# EEM_Connectors.net
KiCad netlist of a schematic drawn in Altium Designer
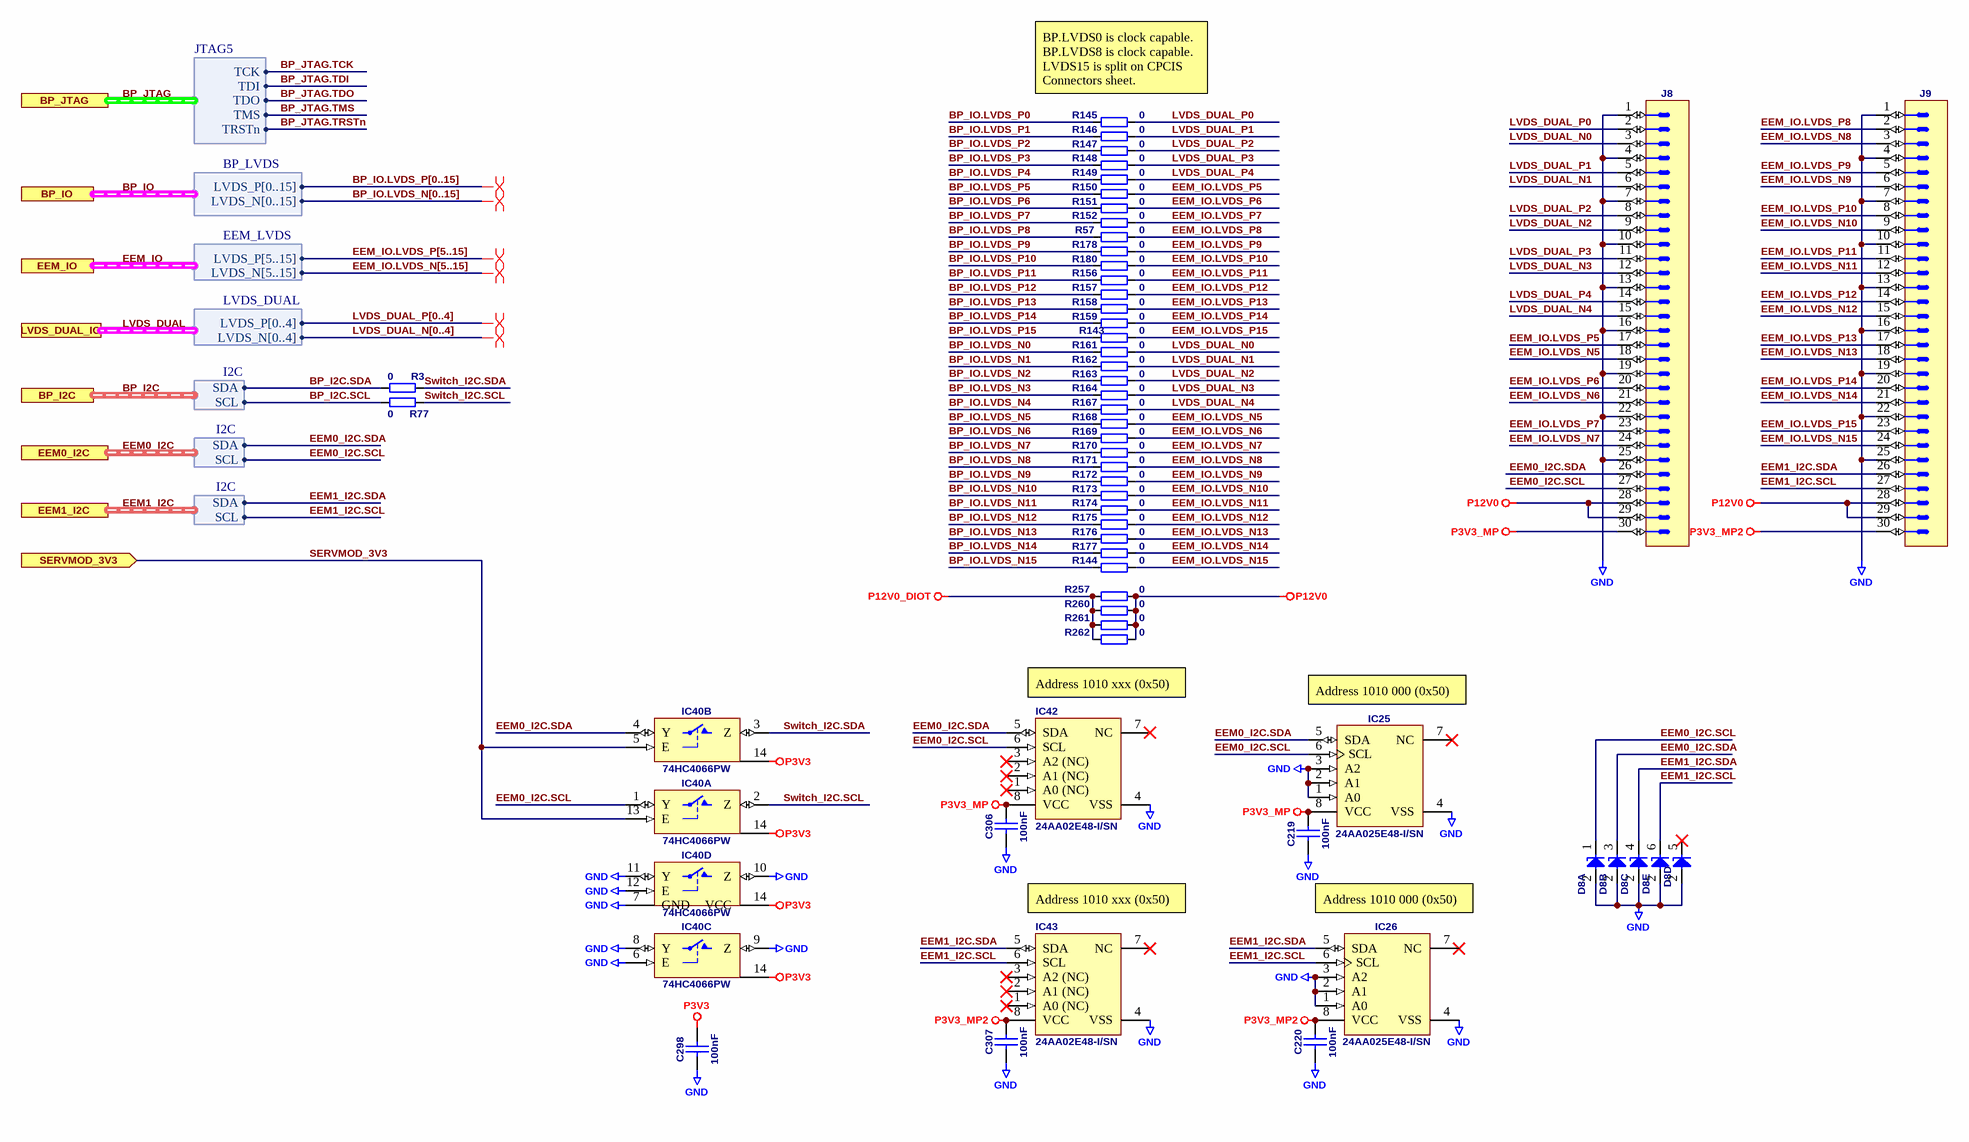
[diagram p0: EEM_Connectors.SchDoc]

(export (version "E")
  (design (tool "Eeschema 10.0.6"))
  (components
    (comp (ref "C219")
      (value "100nF")
      (footprint "CAPC1005X55N")
      (description "Non-polarised capacitor")
      (fields
        (field (name "PART NUMBER") "CC0402_100NF_25V_10%_X7R_YUDEN_TMK105B7104KVHF")
        (field (name "VOLTAGE") "25V")
        (field (name "AUTHOR") "CERN DEM JLC")
      )
      (libsource (lib "Capacitors") (part "Capacitor - non polarized"))
    )
    (comp (ref "C220")
      (value "100nF")
      (footprint "CAPC1005X55N")
      (description "Non-polarised capacitor")
      (fields
        (field (name "PART NUMBER") "CC0402_100NF_16V_10%_X5R")
        (field (name "VOLTAGE") "16V")
        (field (name "AUTHOR") "CERN DEM JLC")
      )
      (libsource (lib "Capacitors") (part "Capacitor - non polarized"))
    )
    (comp (ref "C298")
      (value "100nF")
      (footprint "CAPC1005X55N")
      (description "Non-polarised capacitor")
      (fields
        (field (name "PART NUMBER") "CC0402_100NF_16V_10%_X5R")
        (field (name "VOLTAGE") "16V")
        (field (name "AUTHOR") "CERN DEM JLC")
      )
      (libsource (lib "Capacitors") (part "Capacitor - non polarized"))
    )
    (comp (ref "C306")
      (value "100nF")
      (footprint "CAPC1005X55N")
      (description "Non-polarised capacitor")
      (fields
        (field (name "PART NUMBER") "CC0402_100NF_25V_10%_X7R_YUDEN_TMK105B7104KVHF")
        (field (name "VOLTAGE") "25V")
        (field (name "AUTHOR") "CERN DEM JLC")
      )
      (libsource (lib "Capacitors") (part "Capacitor - non polarized"))
    )
    (comp (ref "C307")
      (value "100nF")
      (footprint "CAPC1005X55N")
      (description "Non-polarised capacitor")
      (fields
        (field (name "PART NUMBER") "CC0402_100NF_25V_10%_X7R_YUDEN_TMK105B7104KVHF")
        (field (name "VOLTAGE") "25V")
        (field (name "AUTHOR") "CERN DEM JLC")
      )
      (libsource (lib "Capacitors") (part "Capacitor - non polarized"))
    )
    (comp (ref "D8")
      (value "PESD3V3L5UY")
      (footprint "SOT65P210X110-6N")
      (description "Fivefold ESD Protection Diode Arrays")
      (fields
        (field (name "VOLTAGE") "3.3V")
        (field (name "POWER") "200W")
        (field (name "AUTHOR") "CERN DEM WB")
      )
      (libsource (lib "ICs And Semiconductors") (part "PESD Array 5diodes 6pins Common anode2"))
    )
    (comp (ref "IC25")
      (value "24AA025E48-I/SN")
      (footprint "SOIC127P600X175-8N")
      (description "1.7V-5.5V, 2K I2C™ Serial EEPROMs with EUI-48™ Node Identity")
      (fields (field (name "MANUFACTURER") "MICROCHIP TECHNOLOGY") (field (name "AUTHOR") "CERN DEM MR"))
      (libsource (lib "ICs And Semiconductors") (part "24AA025E48-I/SN"))
    )
    (comp (ref "IC26")
      (value "24AA025E48-I/SN")
      (footprint "SOIC127P600X175-8N")
      (description "1.7V-5.5V, 2K I2C™ Serial EEPROMs with EUI-48™ Node Identity")
      (fields (field (name "MANUFACTURER") "MICROCHIP TECHNOLOGY") (field (name "AUTHOR") "CERN DEM MR"))
      (libsource (lib "ICs And Semiconductors") (part "24AA025E48-I/SN"))
    )
    (comp (ref "IC40")
      (value "74HC4066PW")
      (footprint "SOP65P640X110-14N")
      (fields (field (name "MANUFACTURER") "NXP SEMICONDUCTORS") (field (name "AUTHOR") "CERN DEM JLC"))
      (libsource (lib "ICs And Semiconductors") (part "4066"))
    )
    (comp (ref "IC42")
      (value "24AA02E48-I/SN")
      (footprint "SOIC127P600X175-8N")
      (description "1.7V-5.5V, 2K I2C™ Serial EEPROMs with EUI-48™ Node Identity")
      (libsource (lib "Integrated_Library_MP") (part "24AA02E48-I/SN"))
    )
    (comp (ref "IC43")
      (value "24AA02E48-I/SN")
      (footprint "SOIC127P600X175-8N")
      (description "1.7V-5.5V, 2K I2C™ Serial EEPROMs with EUI-48™ Node Identity")
      (libsource (lib "Integrated_Library_MP") (part "24AA02E48-I/SN"))
    )
    (comp (ref "J8")
      (value "~")
      (footprint "3M_N2530-6002RB")
      (description "Connector 30 Male")
      (fields
        (field (name "PART NUMBER") "3M_N2530-6002RB")
        (field (name "MANUFACTURER") "3M")
        (field (name "AUTHOR") "CERN DEM JLC")
      )
      (libsource (lib "Connectors") (part "Connector 30 Male"))
    )
    (comp (ref "J9")
      (value "~")
      (footprint "3M_N2530-6002RB")
      (description "Connector 30 Male")
      (fields
        (field (name "PART NUMBER") "3M_N2530-6002RB")
        (field (name "MANUFACTURER") "3M")
        (field (name "AUTHOR") "CERN DEM JLC")
      )
      (libsource (lib "Connectors") (part "Connector 30 Male"))
    )
    (comp (ref "R3")
      (value "0")
      (footprint "RESC1005X40N")
      (description "Resistor")
      (fields
        (field (name "PART NUMBER") "R0402_0R_JUMPER")
        (field (name "MANUFACTURER") "GENERIC")
        (field (name "AUTHOR") "CERN DEM JLC")
      )
      (libsource (lib "Resistors") (part "Resistor"))
    )
    (comp (ref "R57")
      (value "0")
      (footprint "RESC1005X40N")
      (description "Resistor")
      (fields
        (field (name "PART NUMBER") "R0402_0R_JUMPER")
        (field (name "MANUFACTURER") "GENERIC")
        (field (name "AUTHOR") "CERN DEM JLC")
      )
      (libsource (lib "Resistors") (part "Resistor"))
    )
    (comp (ref "R77")
      (value "0")
      (footprint "RESC1005X40N")
      (description "Resistor")
      (fields
        (field (name "PART NUMBER") "R0402_0R_JUMPER")
        (field (name "MANUFACTURER") "GENERIC")
        (field (name "AUTHOR") "CERN DEM JLC")
      )
      (libsource (lib "Resistors") (part "Resistor"))
    )
    (comp (ref "R143")
      (value "0")
      (footprint "RESC1005X40N")
      (description "Resistor")
      (fields
        (field (name "PART NUMBER") "R0402_0R_JUMPER")
        (field (name "MANUFACTURER") "GENERIC")
        (field (name "AUTHOR") "CERN DEM JLC")
      )
      (libsource (lib "Resistors") (part "Resistor"))
    )
    (comp (ref "R144")
      (value "0")
      (footprint "RESC1005X40N")
      (description "Resistor")
      (fields
        (field (name "PART NUMBER") "R0402_0R_JUMPER")
        (field (name "MANUFACTURER") "GENERIC")
        (field (name "AUTHOR") "CERN DEM JLC")
      )
      (libsource (lib "Resistors") (part "Resistor"))
    )
    (comp (ref "R145")
      (value "0")
      (footprint "RESC1005X40N")
      (description "Resistor")
      (fields
        (field (name "PART NUMBER") "R0402_0R_JUMPER")
        (field (name "MANUFACTURER") "GENERIC")
        (field (name "AUTHOR") "CERN DEM JLC")
      )
      (libsource (lib "Resistors") (part "Resistor"))
    )
    (comp (ref "R146")
      (value "0")
      (footprint "RESC1005X40N")
      (description "Resistor")
      (fields
        (field (name "PART NUMBER") "R0402_0R_JUMPER")
        (field (name "MANUFACTURER") "GENERIC")
        (field (name "AUTHOR") "CERN DEM JLC")
      )
      (libsource (lib "Resistors") (part "Resistor"))
    )
    (comp (ref "R147")
      (value "0")
      (footprint "RESC1005X40N")
      (description "Resistor")
      (fields
        (field (name "PART NUMBER") "R0402_0R_JUMPER")
        (field (name "MANUFACTURER") "GENERIC")
        (field (name "AUTHOR") "CERN DEM JLC")
      )
      (libsource (lib "Resistors") (part "Resistor"))
    )
    (comp (ref "R148")
      (value "0")
      (footprint "RESC1005X40N")
      (description "Resistor")
      (fields
        (field (name "PART NUMBER") "R0402_0R_JUMPER")
        (field (name "MANUFACTURER") "GENERIC")
        (field (name "AUTHOR") "CERN DEM JLC")
      )
      (libsource (lib "Resistors") (part "Resistor"))
    )
    (comp (ref "R149")
      (value "0")
      (footprint "RESC1005X40N")
      (description "Resistor")
      (fields
        (field (name "PART NUMBER") "R0402_0R_JUMPER")
        (field (name "MANUFACTURER") "GENERIC")
        (field (name "AUTHOR") "CERN DEM JLC")
      )
      (libsource (lib "Resistors") (part "Resistor"))
    )
    (comp (ref "R150")
      (value "0")
      (footprint "RESC1005X40N")
      (description "Resistor")
      (fields
        (field (name "PART NUMBER") "R0402_0R_JUMPER")
        (field (name "MANUFACTURER") "GENERIC")
        (field (name "AUTHOR") "CERN DEM JLC")
      )
      (libsource (lib "Resistors") (part "Resistor"))
    )
    (comp (ref "R151")
      (value "0")
      (footprint "RESC1005X40N")
      (description "Resistor")
      (fields
        (field (name "PART NUMBER") "R0402_0R_JUMPER")
        (field (name "MANUFACTURER") "GENERIC")
        (field (name "AUTHOR") "CERN DEM JLC")
      )
      (libsource (lib "Resistors") (part "Resistor"))
    )
    (comp (ref "R152")
      (value "0")
      (footprint "RESC1005X40N")
      (description "Resistor")
      (fields
        (field (name "PART NUMBER") "R0402_0R_JUMPER")
        (field (name "MANUFACTURER") "GENERIC")
        (field (name "AUTHOR") "CERN DEM JLC")
      )
      (libsource (lib "Resistors") (part "Resistor"))
    )
    (comp (ref "R156")
      (value "0")
      (footprint "RESC1005X40N")
      (description "Resistor")
      (fields
        (field (name "PART NUMBER") "R0402_0R_JUMPER")
        (field (name "MANUFACTURER") "GENERIC")
        (field (name "AUTHOR") "CERN DEM JLC")
      )
      (libsource (lib "Resistors") (part "Resistor"))
    )
    (comp (ref "R157")
      (value "0")
      (footprint "RESC1005X40N")
      (description "Resistor")
      (fields
        (field (name "PART NUMBER") "R0402_0R_JUMPER")
        (field (name "MANUFACTURER") "GENERIC")
        (field (name "AUTHOR") "CERN DEM JLC")
      )
      (libsource (lib "Resistors") (part "Resistor"))
    )
    (comp (ref "R158")
      (value "0")
      (footprint "RESC1005X40N")
      (description "Resistor")
      (fields
        (field (name "PART NUMBER") "R0402_0R_JUMPER")
        (field (name "MANUFACTURER") "GENERIC")
        (field (name "AUTHOR") "CERN DEM JLC")
      )
      (libsource (lib "Resistors") (part "Resistor"))
    )
    (comp (ref "R159")
      (value "0")
      (footprint "RESC1005X40N")
      (description "Resistor")
      (fields
        (field (name "PART NUMBER") "R0402_0R_JUMPER")
        (field (name "MANUFACTURER") "GENERIC")
        (field (name "AUTHOR") "CERN DEM JLC")
      )
      (libsource (lib "Resistors") (part "Resistor"))
    )
    (comp (ref "R161")
      (value "0")
      (footprint "RESC1005X40N")
      (description "Resistor")
      (fields
        (field (name "PART NUMBER") "R0402_0R_JUMPER")
        (field (name "MANUFACTURER") "GENERIC")
        (field (name "AUTHOR") "CERN DEM JLC")
      )
      (libsource (lib "Resistors") (part "Resistor"))
    )
    (comp (ref "R162")
      (value "0")
      (footprint "RESC1005X40N")
      (description "Resistor")
      (fields
        (field (name "PART NUMBER") "R0402_0R_JUMPER")
        (field (name "MANUFACTURER") "GENERIC")
        (field (name "AUTHOR") "CERN DEM JLC")
      )
      (libsource (lib "Resistors") (part "Resistor"))
    )
    (comp (ref "R163")
      (value "0")
      (footprint "RESC1005X40N")
      (description "Resistor")
      (fields
        (field (name "PART NUMBER") "R0402_0R_JUMPER")
        (field (name "MANUFACTURER") "GENERIC")
        (field (name "AUTHOR") "CERN DEM JLC")
      )
      (libsource (lib "Resistors") (part "Resistor"))
    )
    (comp (ref "R164")
      (value "0")
      (footprint "RESC1005X40N")
      (description "Resistor")
      (fields
        (field (name "PART NUMBER") "R0402_0R_JUMPER")
        (field (name "MANUFACTURER") "GENERIC")
        (field (name "AUTHOR") "CERN DEM JLC")
      )
      (libsource (lib "Resistors") (part "Resistor"))
    )
    (comp (ref "R167")
      (value "0")
      (footprint "RESC1005X40N")
      (description "Resistor")
      (fields
        (field (name "PART NUMBER") "R0402_0R_JUMPER")
        (field (name "MANUFACTURER") "GENERIC")
        (field (name "AUTHOR") "CERN DEM JLC")
      )
      (libsource (lib "Resistors") (part "Resistor"))
    )
    (comp (ref "R168")
      (value "0")
      (footprint "RESC1005X40N")
      (description "Resistor")
      (fields
        (field (name "PART NUMBER") "R0402_0R_JUMPER")
        (field (name "MANUFACTURER") "GENERIC")
        (field (name "AUTHOR") "CERN DEM JLC")
      )
      (libsource (lib "Resistors") (part "Resistor"))
    )
    (comp (ref "R169")
      (value "0")
      (footprint "RESC1005X40N")
      (description "Resistor")
      (fields
        (field (name "PART NUMBER") "R0402_0R_JUMPER")
        (field (name "MANUFACTURER") "GENERIC")
        (field (name "AUTHOR") "CERN DEM JLC")
      )
      (libsource (lib "Resistors") (part "Resistor"))
    )
    (comp (ref "R170")
      (value "0")
      (footprint "RESC1005X40N")
      (description "Resistor")
      (fields
        (field (name "PART NUMBER") "R0402_0R_JUMPER")
        (field (name "MANUFACTURER") "GENERIC")
        (field (name "AUTHOR") "CERN DEM JLC")
      )
      (libsource (lib "Resistors") (part "Resistor"))
    )
    (comp (ref "R171")
      (value "0")
      (footprint "RESC1005X40N")
      (description "Resistor")
      (fields
        (field (name "PART NUMBER") "R0402_0R_JUMPER")
        (field (name "MANUFACTURER") "GENERIC")
        (field (name "AUTHOR") "CERN DEM JLC")
      )
      (libsource (lib "Resistors") (part "Resistor"))
    )
    (comp (ref "R172")
      (value "0")
      (footprint "RESC1005X40N")
      (description "Resistor")
      (fields
        (field (name "PART NUMBER") "R0402_0R_JUMPER")
        (field (name "MANUFACTURER") "GENERIC")
        (field (name "AUTHOR") "CERN DEM JLC")
      )
      (libsource (lib "Resistors") (part "Resistor"))
    )
    (comp (ref "R173")
      (value "0")
      (footprint "RESC1005X40N")
      (description "Resistor")
      (fields
        (field (name "PART NUMBER") "R0402_0R_JUMPER")
        (field (name "MANUFACTURER") "GENERIC")
        (field (name "AUTHOR") "CERN DEM JLC")
      )
      (libsource (lib "Resistors") (part "Resistor"))
    )
    (comp (ref "R174")
      (value "0")
      (footprint "RESC1005X40N")
      (description "Resistor")
      (fields
        (field (name "PART NUMBER") "R0402_0R_JUMPER")
        (field (name "MANUFACTURER") "GENERIC")
        (field (name "AUTHOR") "CERN DEM JLC")
      )
      (libsource (lib "Resistors") (part "Resistor"))
    )
    (comp (ref "R175")
      (value "0")
      (footprint "RESC1005X40N")
      (description "Resistor")
      (fields
        (field (name "PART NUMBER") "R0402_0R_JUMPER")
        (field (name "MANUFACTURER") "GENERIC")
        (field (name "AUTHOR") "CERN DEM JLC")
      )
      (libsource (lib "Resistors") (part "Resistor"))
    )
    (comp (ref "R176")
      (value "0")
      (footprint "RESC1005X40N")
      (description "Resistor")
      (fields
        (field (name "PART NUMBER") "R0402_0R_JUMPER")
        (field (name "MANUFACTURER") "GENERIC")
        (field (name "AUTHOR") "CERN DEM JLC")
      )
      (libsource (lib "Resistors") (part "Resistor"))
    )
    (comp (ref "R177")
      (value "0")
      (footprint "RESC1005X40N")
      (description "Resistor")
      (fields
        (field (name "PART NUMBER") "R0402_0R_JUMPER")
        (field (name "MANUFACTURER") "GENERIC")
        (field (name "AUTHOR") "CERN DEM JLC")
      )
      (libsource (lib "Resistors") (part "Resistor"))
    )
    (comp (ref "R178")
      (value "0")
      (footprint "RESC1005X40N")
      (description "Resistor")
      (fields
        (field (name "PART NUMBER") "R0402_0R_JUMPER")
        (field (name "MANUFACTURER") "GENERIC")
        (field (name "AUTHOR") "CERN DEM JLC")
      )
      (libsource (lib "Resistors") (part "Resistor"))
    )
    (comp (ref "R180")
      (value "0")
      (footprint "RESC1005X40N")
      (description "Resistor")
      (fields
        (field (name "PART NUMBER") "R0402_0R_JUMPER")
        (field (name "MANUFACTURER") "GENERIC")
        (field (name "AUTHOR") "CERN DEM JLC")
      )
      (libsource (lib "Resistors") (part "Resistor"))
    )
    (comp (ref "R257")
      (value "0")
      (footprint "RESC1005X40N")
      (description "Resistor")
      (fields
        (field (name "PART NUMBER") "R0402_0R_JUMPER")
        (field (name "MANUFACTURER") "GENERIC")
        (field (name "AUTHOR") "CERN DEM JLC")
      )
      (libsource (lib "Resistors") (part "Resistor"))
    )
    (comp (ref "R260")
      (value "0")
      (footprint "RESC1005X40N")
      (description "Resistor")
      (fields
        (field (name "PART NUMBER") "R0402_0R_JUMPER")
        (field (name "MANUFACTURER") "GENERIC")
        (field (name "AUTHOR") "CERN DEM JLC")
      )
      (libsource (lib "Resistors") (part "Resistor"))
    )
    (comp (ref "R261")
      (value "0")
      (footprint "RESC1005X40N")
      (description "Resistor")
      (fields
        (field (name "PART NUMBER") "R0402_0R_JUMPER")
        (field (name "MANUFACTURER") "GENERIC")
        (field (name "AUTHOR") "CERN DEM JLC")
      )
      (libsource (lib "Resistors") (part "Resistor"))
    )
    (comp (ref "R262")
      (value "0")
      (footprint "RESC1005X40N")
      (description "Resistor")
      (fields
        (field (name "PART NUMBER") "R0402_0R_JUMPER")
        (field (name "MANUFACTURER") "GENERIC")
        (field (name "AUTHOR") "CERN DEM JLC")
      )
      (libsource (lib "Resistors") (part "Resistor"))
    )
  )
  (nets
    (net (code "8") (name "/BP_I2C.SCL") (class "Default")
      (node (ref "R77") (pin "1") (pinfunction "1_1") (pintype "passive"))
    )
    (net (code "9") (name "/BP_I2C.SDA") (class "Default")
      (node (ref "R3") (pin "1") (pinfunction "1_1") (pintype "passive"))
    )
    (net (code "11") (name "/BP_IO.LVDS_N0") (class "Default")
      (node (ref "R161") (pin "1") (pinfunction "1_1") (pintype "passive"))
    )
    (net (code "12") (name "/BP_IO.LVDS_N1") (class "Default")
      (node (ref "R162") (pin "1") (pinfunction "1_1") (pintype "passive"))
    )
    (net (code "13") (name "/BP_IO.LVDS_N2") (class "Default")
      (node (ref "R163") (pin "1") (pinfunction "1_1") (pintype "passive"))
    )
    (net (code "14") (name "/BP_IO.LVDS_N3") (class "Default")
      (node (ref "R164") (pin "1") (pinfunction "1_1") (pintype "passive"))
    )
    (net (code "15") (name "/BP_IO.LVDS_N4") (class "Default")
      (node (ref "R167") (pin "1") (pinfunction "1_1") (pintype "passive"))
    )
    (net (code "16") (name "/BP_IO.LVDS_N5") (class "Default")
      (node (ref "R168") (pin "1") (pinfunction "1_1") (pintype "passive"))
    )
    (net (code "17") (name "/BP_IO.LVDS_N6") (class "Default")
      (node (ref "R169") (pin "1") (pinfunction "1_1") (pintype "passive"))
    )
    (net (code "18") (name "/BP_IO.LVDS_N7") (class "Default")
      (node (ref "R170") (pin "1") (pinfunction "1_1") (pintype "passive"))
    )
    (net (code "19") (name "/BP_IO.LVDS_N8") (class "Default")
      (node (ref "R171") (pin "1") (pinfunction "1_1") (pintype "passive"))
    )
    (net (code "20") (name "/BP_IO.LVDS_N9") (class "Default")
      (node (ref "R172") (pin "1") (pinfunction "1_1") (pintype "passive"))
    )
    (net (code "21") (name "/BP_IO.LVDS_N10") (class "Default")
      (node (ref "R173") (pin "1") (pinfunction "1_1") (pintype "passive"))
    )
    (net (code "22") (name "/BP_IO.LVDS_N11") (class "Default")
      (node (ref "R174") (pin "1") (pinfunction "1_1") (pintype "passive"))
    )
    (net (code "23") (name "/BP_IO.LVDS_N12") (class "Default")
      (node (ref "R175") (pin "1") (pinfunction "1_1") (pintype "passive"))
    )
    (net (code "24") (name "/BP_IO.LVDS_N13") (class "Default")
      (node (ref "R176") (pin "1") (pinfunction "1_1") (pintype "passive"))
    )
    (net (code "25") (name "/BP_IO.LVDS_N14") (class "Default")
      (node (ref "R177") (pin "1") (pinfunction "1_1") (pintype "passive"))
    )
    (net (code "26") (name "/BP_IO.LVDS_N15") (class "Default")
      (node (ref "R144") (pin "1") (pinfunction "1_1") (pintype "passive"))
    )
    (net (code "28") (name "/BP_IO.LVDS_P0") (class "Default")
      (node (ref "R145") (pin "1") (pinfunction "1_1") (pintype "passive"))
    )
    (net (code "29") (name "/BP_IO.LVDS_P1") (class "Default")
      (node (ref "R146") (pin "1") (pinfunction "1_1") (pintype "passive"))
    )
    (net (code "30") (name "/BP_IO.LVDS_P2") (class "Default")
      (node (ref "R147") (pin "1") (pinfunction "1_1") (pintype "passive"))
    )
    (net (code "31") (name "/BP_IO.LVDS_P3") (class "Default")
      (node (ref "R148") (pin "1") (pinfunction "1_1") (pintype "passive"))
    )
    (net (code "32") (name "/BP_IO.LVDS_P4") (class "Default")
      (node (ref "R149") (pin "1") (pinfunction "1_1") (pintype "passive"))
    )
    (net (code "33") (name "/BP_IO.LVDS_P5") (class "Default")
      (node (ref "R150") (pin "1") (pinfunction "1_1") (pintype "passive"))
    )
    (net (code "34") (name "/BP_IO.LVDS_P6") (class "Default")
      (node (ref "R151") (pin "1") (pinfunction "1_1") (pintype "passive"))
    )
    (net (code "35") (name "/BP_IO.LVDS_P7") (class "Default")
      (node (ref "R152") (pin "1") (pinfunction "1_1") (pintype "passive"))
    )
    (net (code "36") (name "/BP_IO.LVDS_P8") (class "Default")
      (node (ref "R57") (pin "1") (pinfunction "1_1") (pintype "passive"))
    )
    (net (code "37") (name "/BP_IO.LVDS_P9") (class "Default")
      (node (ref "R178") (pin "1") (pinfunction "1_1") (pintype "passive"))
    )
    (net (code "38") (name "/BP_IO.LVDS_P10") (class "Default")
      (node (ref "R180") (pin "1") (pinfunction "1_1") (pintype "passive"))
    )
    (net (code "39") (name "/BP_IO.LVDS_P11") (class "Default")
      (node (ref "R156") (pin "1") (pinfunction "1_1") (pintype "passive"))
    )
    (net (code "40") (name "/BP_IO.LVDS_P12") (class "Default")
      (node (ref "R157") (pin "1") (pinfunction "1_1") (pintype "passive"))
    )
    (net (code "41") (name "/BP_IO.LVDS_P13") (class "Default")
      (node (ref "R158") (pin "1") (pinfunction "1_1") (pintype "passive"))
    )
    (net (code "42") (name "/BP_IO.LVDS_P14") (class "Default")
      (node (ref "R159") (pin "1") (pinfunction "1_1") (pintype "passive"))
    )
    (net (code "43") (name "/BP_IO.LVDS_P15") (class "Default")
      (node (ref "R143") (pin "1") (pinfunction "1_1") (pintype "passive"))
    )
    (net (code "50") (name "/EEM0_I2C.SCL") (class "Default")
      (node (ref "D8") (pin "1") (pinfunction "C_1") (pintype "passive"))
      (node (ref "IC25") (pin "6") (pinfunction "SCL_6") (pintype "input"))
      (node (ref "IC40") (pin "1") (pinfunction "Y_1") (pintype "bidirectional"))
      (node (ref "IC42") (pin "6") (pinfunction "SCL_6") (pintype "input"))
      (node (ref "J8") (pin "27") (pinfunction "27_27") (pintype "bidirectional"))
    )
    (net (code "51") (name "/EEM0_I2C.SDA") (class "Default")
      (node (ref "D8") (pin "3") (pinfunction "C_3") (pintype "passive"))
      (node (ref "IC25") (pin "5") (pinfunction "SDA_5") (pintype "bidirectional"))
      (node (ref "IC40") (pin "4") (pinfunction "Y_4") (pintype "bidirectional"))
      (node (ref "IC42") (pin "5") (pinfunction "SDA_5") (pintype "bidirectional"))
      (node (ref "J8") (pin "26") (pinfunction "26_26") (pintype "bidirectional"))
    )
    (net (code "53") (name "/EEM1_I2C.SCL") (class "Default")
      (node (ref "D8") (pin "6") (pinfunction "C_6") (pintype "passive"))
      (node (ref "IC26") (pin "6") (pinfunction "SCL_6") (pintype "input"))
      (node (ref "IC43") (pin "6") (pinfunction "SCL_6") (pintype "input"))
      (node (ref "J9") (pin "27") (pinfunction "27_27") (pintype "bidirectional"))
    )
    (net (code "54") (name "/EEM1_I2C.SDA") (class "Default")
      (node (ref "D8") (pin "4") (pinfunction "C_4") (pintype "passive"))
      (node (ref "IC26") (pin "5") (pinfunction "SDA_5") (pintype "bidirectional"))
      (node (ref "IC43") (pin "5") (pinfunction "SDA_5") (pintype "bidirectional"))
      (node (ref "J9") (pin "26") (pinfunction "26_26") (pintype "bidirectional"))
    )
    (net (code "56") (name "/EEM_IO.LVDS_N5") (class "Default")
      (node (ref "J8") (pin "18") (pinfunction "18_18") (pintype "bidirectional"))
      (node (ref "R168") (pin "2") (pinfunction "2_2") (pintype "passive"))
    )
    (net (code "57") (name "/EEM_IO.LVDS_N6") (class "Default")
      (node (ref "J8") (pin "21") (pinfunction "21_21") (pintype "bidirectional"))
      (node (ref "R169") (pin "2") (pinfunction "2_2") (pintype "passive"))
    )
    (net (code "58") (name "/EEM_IO.LVDS_N7") (class "Default")
      (node (ref "J8") (pin "24") (pinfunction "24_24") (pintype "bidirectional"))
      (node (ref "R170") (pin "2") (pinfunction "2_2") (pintype "passive"))
    )
    (net (code "59") (name "/EEM_IO.LVDS_N8") (class "Default")
      (node (ref "J9") (pin "3") (pinfunction "3_3") (pintype "bidirectional"))
      (node (ref "R171") (pin "2") (pinfunction "2_2") (pintype "passive"))
    )
    (net (code "60") (name "/EEM_IO.LVDS_N9") (class "Default")
      (node (ref "J9") (pin "6") (pinfunction "6_6") (pintype "bidirectional"))
      (node (ref "R172") (pin "2") (pinfunction "2_2") (pintype "passive"))
    )
    (net (code "61") (name "/EEM_IO.LVDS_N10") (class "Default")
      (node (ref "J9") (pin "9") (pinfunction "9_9") (pintype "bidirectional"))
      (node (ref "R173") (pin "2") (pinfunction "2_2") (pintype "passive"))
    )
    (net (code "62") (name "/EEM_IO.LVDS_N11") (class "Default")
      (node (ref "J9") (pin "12") (pinfunction "12_12") (pintype "bidirectional"))
      (node (ref "R174") (pin "2") (pinfunction "2_2") (pintype "passive"))
    )
    (net (code "63") (name "/EEM_IO.LVDS_N12") (class "Default")
      (node (ref "J9") (pin "15") (pinfunction "15_15") (pintype "bidirectional"))
      (node (ref "R175") (pin "2") (pinfunction "2_2") (pintype "passive"))
    )
    (net (code "64") (name "/EEM_IO.LVDS_N13") (class "Default")
      (node (ref "J9") (pin "18") (pinfunction "18_18") (pintype "bidirectional"))
      (node (ref "R176") (pin "2") (pinfunction "2_2") (pintype "passive"))
    )
    (net (code "65") (name "/EEM_IO.LVDS_N14") (class "Default")
      (node (ref "J9") (pin "21") (pinfunction "21_21") (pintype "bidirectional"))
      (node (ref "R177") (pin "2") (pinfunction "2_2") (pintype "passive"))
    )
    (net (code "66") (name "/EEM_IO.LVDS_N15") (class "Default")
      (node (ref "J9") (pin "24") (pinfunction "24_24") (pintype "bidirectional"))
      (node (ref "R144") (pin "2") (pinfunction "2_2") (pintype "passive"))
    )
    (net (code "67") (name "/EEM_IO.LVDS_P5") (class "Default")
      (node (ref "J8") (pin "17") (pinfunction "17_17") (pintype "bidirectional"))
      (node (ref "R150") (pin "2") (pinfunction "2_2") (pintype "passive"))
    )
    (net (code "68") (name "/EEM_IO.LVDS_P6") (class "Default")
      (node (ref "J8") (pin "20") (pinfunction "20_20") (pintype "bidirectional"))
      (node (ref "R151") (pin "2") (pinfunction "2_2") (pintype "passive"))
    )
    (net (code "69") (name "/EEM_IO.LVDS_P7") (class "Default")
      (node (ref "J8") (pin "23") (pinfunction "23_23") (pintype "bidirectional"))
      (node (ref "R152") (pin "2") (pinfunction "2_2") (pintype "passive"))
    )
    (net (code "70") (name "/EEM_IO.LVDS_P8") (class "Default")
      (node (ref "J9") (pin "2") (pinfunction "2_2") (pintype "bidirectional"))
      (node (ref "R57") (pin "2") (pinfunction "2_2") (pintype "passive"))
    )
    (net (code "71") (name "/EEM_IO.LVDS_P9") (class "Default")
      (node (ref "J9") (pin "5") (pinfunction "5_5") (pintype "bidirectional"))
      (node (ref "R178") (pin "2") (pinfunction "2_2") (pintype "passive"))
    )
    (net (code "72") (name "/EEM_IO.LVDS_P10") (class "Default")
      (node (ref "J9") (pin "8") (pinfunction "8_8") (pintype "bidirectional"))
      (node (ref "R180") (pin "2") (pinfunction "2_2") (pintype "passive"))
    )
    (net (code "73") (name "/EEM_IO.LVDS_P11") (class "Default")
      (node (ref "J9") (pin "11") (pinfunction "11_11") (pintype "bidirectional"))
      (node (ref "R156") (pin "2") (pinfunction "2_2") (pintype "passive"))
    )
    (net (code "74") (name "/EEM_IO.LVDS_P12") (class "Default")
      (node (ref "J9") (pin "14") (pinfunction "14_14") (pintype "bidirectional"))
      (node (ref "R157") (pin "2") (pinfunction "2_2") (pintype "passive"))
    )
    (net (code "75") (name "/EEM_IO.LVDS_P13") (class "Default")
      (node (ref "J9") (pin "17") (pinfunction "17_17") (pintype "bidirectional"))
      (node (ref "R158") (pin "2") (pinfunction "2_2") (pintype "passive"))
    )
    (net (code "76") (name "/EEM_IO.LVDS_P14") (class "Default")
      (node (ref "J9") (pin "20") (pinfunction "20_20") (pintype "bidirectional"))
      (node (ref "R159") (pin "2") (pinfunction "2_2") (pintype "passive"))
    )
    (net (code "77") (name "/EEM_IO.LVDS_P15") (class "Default")
      (node (ref "J9") (pin "23") (pinfunction "23_23") (pintype "bidirectional"))
      (node (ref "R143") (pin "2") (pinfunction "2_2") (pintype "passive"))
    )
    (net (code "79") (name "/LVDS_DUAL_N0") (class "Default")
      (node (ref "J8") (pin "3") (pinfunction "3_3") (pintype "bidirectional"))
      (node (ref "R161") (pin "2") (pinfunction "2_2") (pintype "passive"))
    )
    (net (code "80") (name "/LVDS_DUAL_N1") (class "Default")
      (node (ref "J8") (pin "6") (pinfunction "6_6") (pintype "bidirectional"))
      (node (ref "R162") (pin "2") (pinfunction "2_2") (pintype "passive"))
    )
    (net (code "81") (name "/LVDS_DUAL_N2") (class "Default")
      (node (ref "J8") (pin "9") (pinfunction "9_9") (pintype "bidirectional"))
      (node (ref "R163") (pin "2") (pinfunction "2_2") (pintype "passive"))
    )
    (net (code "82") (name "/LVDS_DUAL_N3") (class "Default")
      (node (ref "J8") (pin "12") (pinfunction "12_12") (pintype "bidirectional"))
      (node (ref "R164") (pin "2") (pinfunction "2_2") (pintype "passive"))
    )
    (net (code "83") (name "/LVDS_DUAL_N4") (class "Default")
      (node (ref "J8") (pin "15") (pinfunction "15_15") (pintype "bidirectional"))
      (node (ref "R167") (pin "2") (pinfunction "2_2") (pintype "passive"))
    )
    (net (code "85") (name "/LVDS_DUAL_P0") (class "Default")
      (node (ref "J8") (pin "2") (pinfunction "2_2") (pintype "bidirectional"))
      (node (ref "R145") (pin "2") (pinfunction "2_2") (pintype "passive"))
    )
    (net (code "86") (name "/LVDS_DUAL_P1") (class "Default")
      (node (ref "J8") (pin "5") (pinfunction "5_5") (pintype "bidirectional"))
      (node (ref "R146") (pin "2") (pinfunction "2_2") (pintype "passive"))
    )
    (net (code "87") (name "/LVDS_DUAL_P2") (class "Default")
      (node (ref "J8") (pin "8") (pinfunction "8_8") (pintype "bidirectional"))
      (node (ref "R147") (pin "2") (pinfunction "2_2") (pintype "passive"))
    )
    (net (code "88") (name "/LVDS_DUAL_P3") (class "Default")
      (node (ref "J8") (pin "11") (pinfunction "11_11") (pintype "bidirectional"))
      (node (ref "R148") (pin "2") (pinfunction "2_2") (pintype "passive"))
    )
    (net (code "89") (name "/LVDS_DUAL_P4") (class "Default")
      (node (ref "J8") (pin "14") (pinfunction "14_14") (pintype "bidirectional"))
      (node (ref "R149") (pin "2") (pinfunction "2_2") (pintype "passive"))
    )
    (net (code "92") (name "/SERVMOD_3V3") (class "Default")
      (node (ref "IC40") (pin "13") (pinfunction "E_13") (pintype "input"))
      (node (ref "IC40") (pin "5") (pinfunction "E_5") (pintype "input"))
    )
    (net (code "93") (name "/Switch_I2C.SCL") (class "Default")
      (node (ref "IC40") (pin "2") (pinfunction "Z_2") (pintype "bidirectional"))
      (node (ref "R77") (pin "2") (pinfunction "2_2") (pintype "passive"))
    )
    (net (code "94") (name "/Switch_I2C.SDA") (class "Default")
      (node (ref "IC40") (pin "3") (pinfunction "Z_3") (pintype "bidirectional"))
      (node (ref "R3") (pin "2") (pinfunction "2_2") (pintype "passive"))
    )
    (net (code "98") (name "GND") (class "Default")
      (node (ref "C219") (pin "1") (pinfunction "1_1") (pintype "passive"))
      (node (ref "C220") (pin "1") (pinfunction "1_1") (pintype "passive"))
      (node (ref "C298") (pin "1") (pinfunction "1_1") (pintype "passive"))
      (node (ref "C306") (pin "1") (pinfunction "1_1") (pintype "passive"))
      (node (ref "C307") (pin "1") (pinfunction "1_1") (pintype "passive"))
      (node (ref "D8") (pin "2") (pinfunction "A_2") (pintype "passive"))
      (node (ref "IC25") (pin "1") (pinfunction "A0_1") (pintype "input"))
      (node (ref "IC25") (pin "2") (pinfunction "A1_2") (pintype "input"))
      (node (ref "IC25") (pin "3") (pinfunction "A2_3") (pintype "input"))
      (node (ref "IC25") (pin "4") (pinfunction "VSS_4") (pintype "power_in"))
      (node (ref "IC26") (pin "1") (pinfunction "A0_1") (pintype "input"))
      (node (ref "IC26") (pin "2") (pinfunction "A1_2") (pintype "input"))
      (node (ref "IC26") (pin "3") (pinfunction "A2_3") (pintype "input"))
      (node (ref "IC26") (pin "4") (pinfunction "VSS_4") (pintype "power_in"))
      (node (ref "IC40") (pin "10") (pinfunction "Z_10") (pintype "bidirectional"))
      (node (ref "IC40") (pin "11") (pinfunction "Y_11") (pintype "bidirectional"))
      (node (ref "IC40") (pin "12") (pinfunction "E_12") (pintype "input"))
      (node (ref "IC40") (pin "6") (pinfunction "E_6") (pintype "input"))
      (node (ref "IC40") (pin "7") (pinfunction "GND_7") (pintype "power_in"))
      (node (ref "IC40") (pin "8") (pinfunction "Y_8") (pintype "bidirectional"))
      (node (ref "IC40") (pin "9") (pinfunction "Z_9") (pintype "bidirectional"))
      (node (ref "IC42") (pin "4") (pinfunction "VSS_4") (pintype "passive"))
      (node (ref "IC43") (pin "4") (pinfunction "VSS_4") (pintype "passive"))
      (node (ref "J8") (pin "1") (pinfunction "1_1") (pintype "bidirectional"))
      (node (ref "J8") (pin "10") (pinfunction "10_10") (pintype "bidirectional"))
      (node (ref "J8") (pin "13") (pinfunction "13_13") (pintype "bidirectional"))
      (node (ref "J8") (pin "16") (pinfunction "16_16") (pintype "bidirectional"))
      (node (ref "J8") (pin "19") (pinfunction "19_19") (pintype "bidirectional"))
      (node (ref "J8") (pin "22") (pinfunction "22_22") (pintype "bidirectional"))
      (node (ref "J8") (pin "25") (pinfunction "25_25") (pintype "bidirectional"))
      (node (ref "J8") (pin "4") (pinfunction "4_4") (pintype "bidirectional"))
      (node (ref "J8") (pin "7") (pinfunction "7_7") (pintype "bidirectional"))
      (node (ref "J9") (pin "1") (pinfunction "1_1") (pintype "bidirectional"))
      (node (ref "J9") (pin "10") (pinfunction "10_10") (pintype "bidirectional"))
      (node (ref "J9") (pin "13") (pinfunction "13_13") (pintype "bidirectional"))
      (node (ref "J9") (pin "16") (pinfunction "16_16") (pintype "bidirectional"))
      (node (ref "J9") (pin "19") (pinfunction "19_19") (pintype "bidirectional"))
      (node (ref "J9") (pin "22") (pinfunction "22_22") (pintype "bidirectional"))
      (node (ref "J9") (pin "25") (pinfunction "25_25") (pintype "bidirectional"))
      (node (ref "J9") (pin "4") (pinfunction "4_4") (pintype "bidirectional"))
      (node (ref "J9") (pin "7") (pinfunction "7_7") (pintype "bidirectional"))
    )
    (net (code "99") (name "P3V3") (class "Default")
      (node (ref "C298") (pin "2") (pinfunction "2_2") (pintype "passive"))
      (node (ref "IC40") (pin "14") (pinfunction "VCC_14") (pintype "power_in"))
    )
    (net (code "100") (name "P3V3_MP") (class "Default")
      (node (ref "C219") (pin "2") (pinfunction "2_2") (pintype "passive"))
      (node (ref "C306") (pin "2") (pinfunction "2_2") (pintype "passive"))
      (node (ref "IC25") (pin "8") (pinfunction "VCC_8") (pintype "power_in"))
      (node (ref "IC42") (pin "8") (pinfunction "VCC_8") (pintype "passive"))
      (node (ref "J8") (pin "30") (pinfunction "30_30") (pintype "bidirectional"))
    )
    (net (code "101") (name "P3V3_MP2") (class "Default")
      (node (ref "C220") (pin "2") (pinfunction "2_2") (pintype "passive"))
      (node (ref "C307") (pin "2") (pinfunction "2_2") (pintype "passive"))
      (node (ref "IC26") (pin "8") (pinfunction "VCC_8") (pintype "power_in"))
      (node (ref "IC43") (pin "8") (pinfunction "VCC_8") (pintype "passive"))
      (node (ref "J9") (pin "30") (pinfunction "30_30") (pintype "bidirectional"))
    )
    (net (code "102") (name "P12V0") (class "Default")
      (node (ref "J8") (pin "28") (pinfunction "28_28") (pintype "bidirectional"))
      (node (ref "J8") (pin "29") (pinfunction "29_29") (pintype "bidirectional"))
      (node (ref "J9") (pin "28") (pinfunction "28_28") (pintype "bidirectional"))
      (node (ref "J9") (pin "29") (pinfunction "29_29") (pintype "bidirectional"))
      (node (ref "R257") (pin "2") (pinfunction "2_2") (pintype "passive"))
      (node (ref "R260") (pin "2") (pinfunction "2_2") (pintype "passive"))
      (node (ref "R261") (pin "2") (pinfunction "2_2") (pintype "passive"))
      (node (ref "R262") (pin "2") (pinfunction "2_2") (pintype "passive"))
    )
    (net (code "103") (name "P12V0_DIOT") (class "Default")
      (node (ref "R257") (pin "1") (pinfunction "1_1") (pintype "passive"))
      (node (ref "R260") (pin "1") (pinfunction "1_1") (pintype "passive"))
      (node (ref "R261") (pin "1") (pinfunction "1_1") (pintype "passive"))
      (node (ref "R262") (pin "1") (pinfunction "1_1") (pintype "passive"))
    )
    (net (code "104") (name "unconnected-(D8D-C-Pad5)") (class "Default")
      (node (ref "D8") (pin "5") (pinfunction "C_5") (pintype "passive+no_connect"))
    )
    (net (code "105") (name "unconnected-(IC25-NC-Pad7)") (class "Default")
      (node (ref "IC25") (pin "7") (pinfunction "NC_7") (pintype "passive+no_connect"))
    )
    (net (code "106") (name "unconnected-(IC26-NC-Pad7)") (class "Default")
      (node (ref "IC26") (pin "7") (pinfunction "NC_7") (pintype "passive+no_connect"))
    )
    (net (code "107") (name "unconnected-(IC42-A0_(NC)-Pad1)") (class "Default")
      (node (ref "IC42") (pin "1") (pinfunction "A0_(NC)_1") (pintype "input+no_connect"))
    )
    (net (code "108") (name "unconnected-(IC42-A1_(NC)-Pad2)") (class "Default")
      (node (ref "IC42") (pin "2") (pinfunction "A1_(NC)_2") (pintype "input+no_connect"))
    )
    (net (code "109") (name "unconnected-(IC42-A2_(NC)-Pad3)") (class "Default")
      (node (ref "IC42") (pin "3") (pinfunction "A2_(NC)_3") (pintype "input+no_connect"))
    )
    (net (code "110") (name "unconnected-(IC42-NC-Pad7)") (class "Default")
      (node (ref "IC42") (pin "7") (pinfunction "NC_7") (pintype "passive+no_connect"))
    )
    (net (code "111") (name "unconnected-(IC43-A0_(NC)-Pad1)") (class "Default")
      (node (ref "IC43") (pin "1") (pinfunction "A0_(NC)_1") (pintype "input+no_connect"))
    )
    (net (code "112") (name "unconnected-(IC43-A1_(NC)-Pad2)") (class "Default")
      (node (ref "IC43") (pin "2") (pinfunction "A1_(NC)_2") (pintype "input+no_connect"))
    )
    (net (code "113") (name "unconnected-(IC43-A2_(NC)-Pad3)") (class "Default")
      (node (ref "IC43") (pin "3") (pinfunction "A2_(NC)_3") (pintype "input+no_connect"))
    )
    (net (code "114") (name "unconnected-(IC43-NC-Pad7)") (class "Default")
      (node (ref "IC43") (pin "7") (pinfunction "NC_7") (pintype "passive+no_connect"))
    )
  )
)
